# kugarem.net
KiCad netlist of a schematic drawn in EAGLE
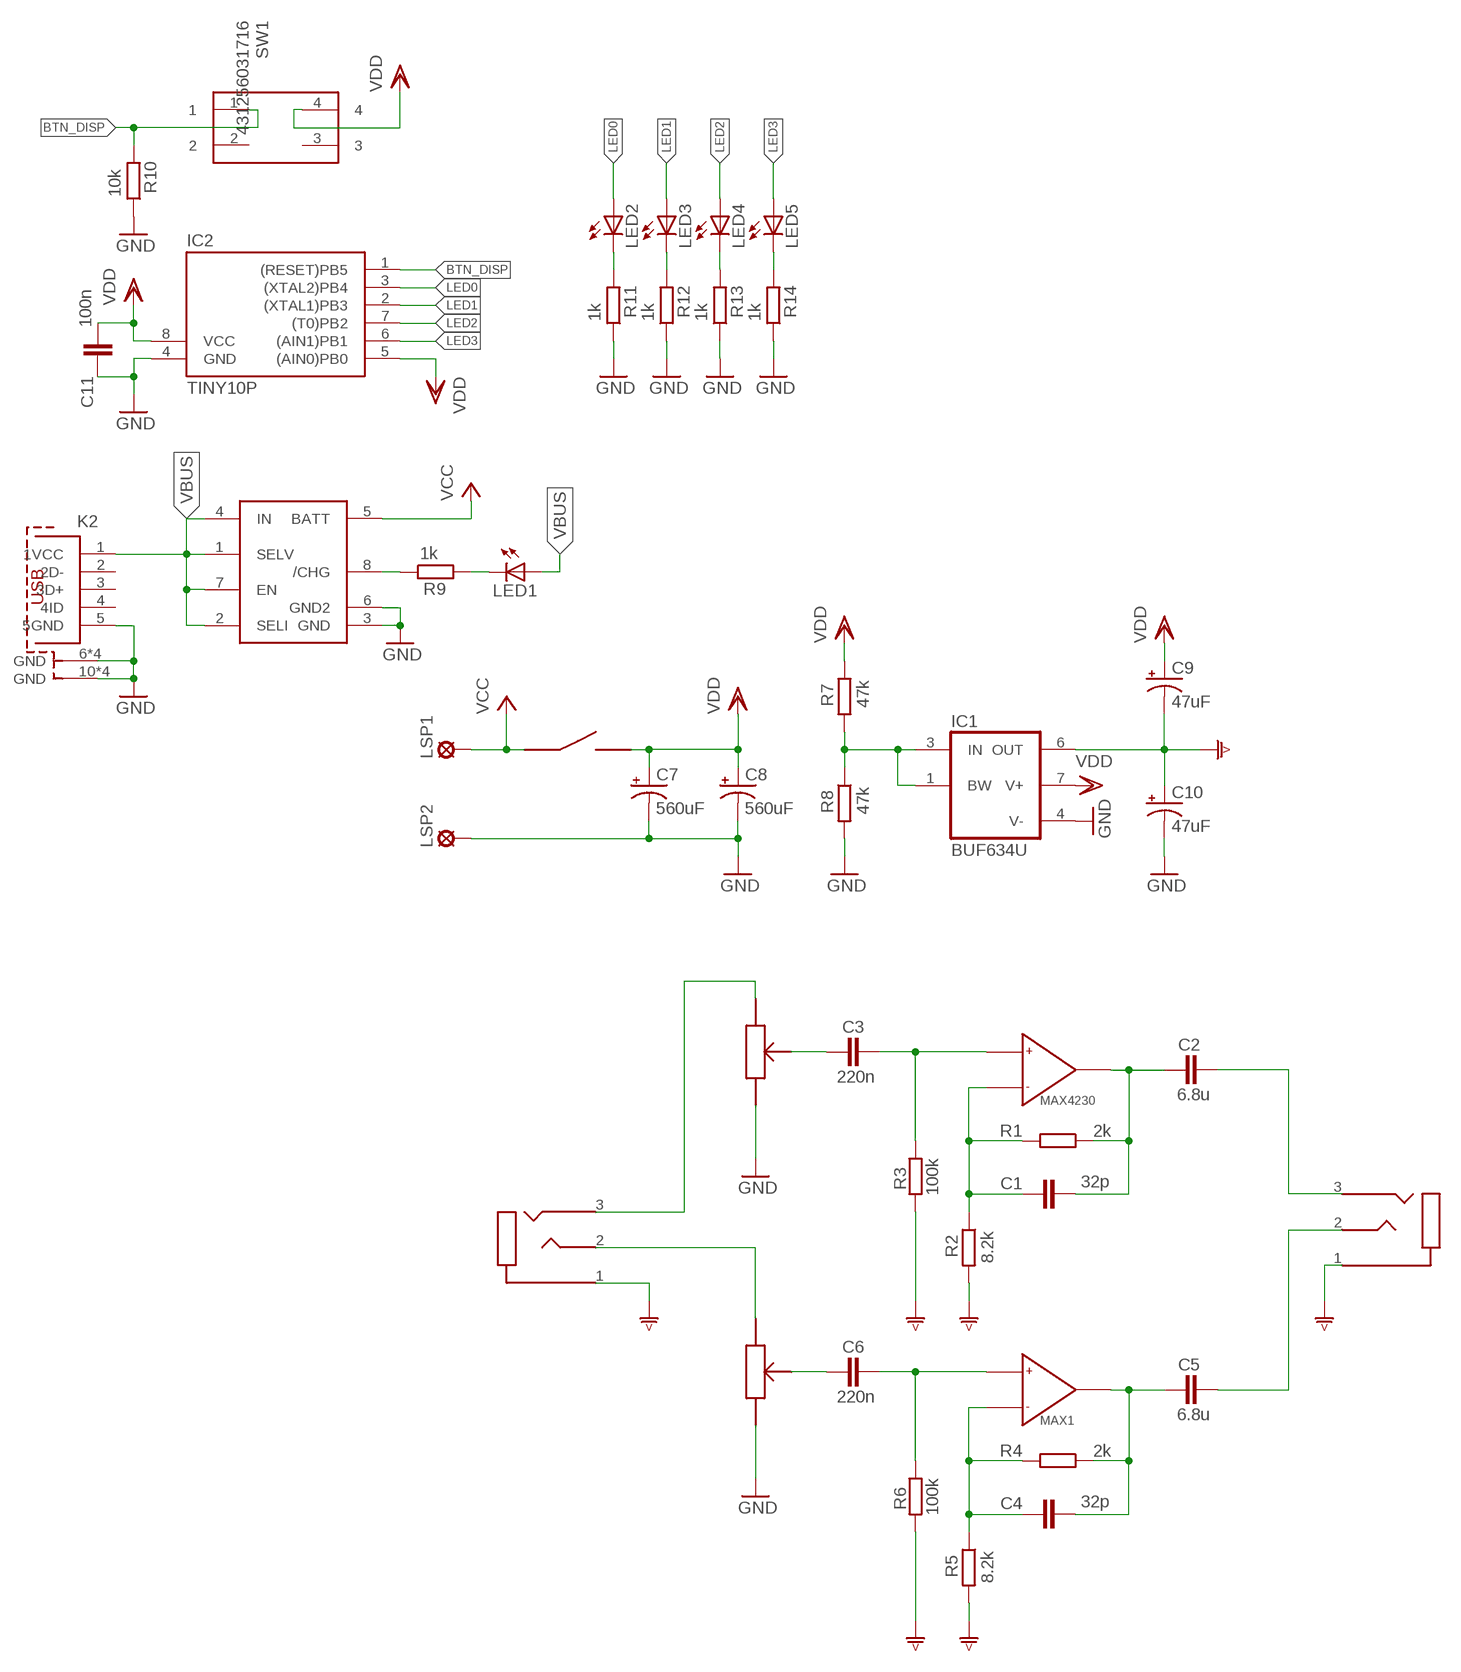
[diagram p0: schematic, sheet 1]

(export (version "E")
  (design (tool "Eeschema 10.0.6"))
  (components
    (comp (ref "C1")
      (value "32p")
      (footprint "eagle-import:C1206")
      (libsource (lib "eagle-import") (part "C-EUC1206"))
    )
    (comp (ref "C2")
      (value "6.8u")
      (footprint "eagle-import:C1206")
      (libsource (lib "eagle-import") (part "C-EUC1206"))
    )
    (comp (ref "C3")
      (value "220n")
      (footprint "eagle-import:C1206")
      (libsource (lib "eagle-import") (part "C-EUC1206"))
    )
    (comp (ref "C4")
      (value "32p")
      (footprint "eagle-import:C1206")
      (libsource (lib "eagle-import") (part "C-EUC1206"))
    )
    (comp (ref "C5")
      (value "6.8u")
      (footprint "eagle-import:C1206")
      (libsource (lib "eagle-import") (part "C-EUC1206"))
    )
    (comp (ref "C6")
      (value "220n")
      (footprint "eagle-import:C1206")
      (libsource (lib "eagle-import") (part "C-EUC1206"))
    )
    (comp (ref "C7")
      (value "560uF")
      (footprint "eagle-import:PANASONIC_G")
      (libsource (lib "eagle-import") (part "560UF-PANASONIC_G-25V-20%"))
    )
    (comp (ref "C8")
      (value "560uF")
      (footprint "eagle-import:PANASONIC_G")
      (libsource (lib "eagle-import") (part "560UF-PANASONIC_G-25V-20%"))
    )
    (comp (ref "C9")
      (value "47uF")
      (footprint "eagle-import:PANASONIC_D")
      (libsource (lib "eagle-import") (part "47UF-POLAR-PANASONIC_D-35V-20%"))
    )
    (comp (ref "C10")
      (value "47uF")
      (footprint "eagle-import:PANASONIC_D")
      (libsource (lib "eagle-import") (part "47UF-POLAR-PANASONIC_D-35V-20%"))
    )
    (comp (ref "C11")
      (value "100n")
      (footprint "eagle-import:C1206")
      (libsource (lib "eagle-import") (part "C-EUC1206"))
    )
    (comp (ref "IC1")
      (value "BUF634U")
      (footprint "eagle-import:SO08")
      (fields (field (name "MF") "TEXAS INSTRUMENTS"))
      (libsource (lib "eagle-import") (part "BUF634U"))
    )
    (comp (ref "IC2")
      (value "TINY10P")
      (footprint "eagle-import:DIL08")
      (libsource (lib "eagle-import") (part "TINY10P"))
    )
    (comp (ref "K2")
      (value "629105150921")
      (footprint "eagle-import:629105150921")
      (libsource (lib "eagle-import") (part "629105150921"))
    )
    (comp (ref "LED1")
      (value "LEDCHIPLED_1206")
      (footprint "eagle-import:CHIPLED_1206")
      (libsource (lib "eagle-import") (part "LEDCHIPLED_1206"))
    )
    (comp (ref "LED2")
      (value "LEDCHIPLED_1206")
      (footprint "eagle-import:CHIPLED_1206")
      (libsource (lib "eagle-import") (part "LEDCHIPLED_1206"))
    )
    (comp (ref "LED3")
      (value "LEDCHIPLED_1206")
      (footprint "eagle-import:CHIPLED_1206")
      (libsource (lib "eagle-import") (part "LEDCHIPLED_1206"))
    )
    (comp (ref "LED4")
      (value "LEDCHIPLED_1206")
      (footprint "eagle-import:CHIPLED_1206")
      (libsource (lib "eagle-import") (part "LEDCHIPLED_1206"))
    )
    (comp (ref "LED5")
      (value "LEDCHIPLED_1206")
      (footprint "eagle-import:CHIPLED_1206")
      (libsource (lib "eagle-import") (part "LEDCHIPLED_1206"))
    )
    (comp (ref "LSP1")
      (value "LSP10")
      (footprint "eagle-import:LSP10")
      (libsource (lib "eagle-import") (part "LSP10"))
    )
    (comp (ref "LSP2")
      (value "LSP10")
      (footprint "eagle-import:LSP10")
      (libsource (lib "eagle-import") (part "LSP10"))
    )
    (comp (ref "MAX1")
      (value "MAX4230")
      (footprint "eagle-import:SOT23-5L")
      (libsource (lib "eagle-import") (part "MAX4230"))
    )
    (comp (ref "MAX4230")
      (value "MAX4230")
      (footprint "eagle-import:SOT23-5L")
      (libsource (lib "eagle-import") (part "MAX4230"))
    )
    (comp (ref "R1")
      (value "2k")
      (footprint "eagle-import:R1206")
      (libsource (lib "eagle-import") (part "R-EU_R1206"))
    )
    (comp (ref "R2")
      (value "8.2k")
      (footprint "eagle-import:R1206")
      (libsource (lib "eagle-import") (part "R-EU_R1206"))
    )
    (comp (ref "R3")
      (value "100k")
      (footprint "eagle-import:R1206")
      (libsource (lib "eagle-import") (part "R-EU_R1206"))
    )
    (comp (ref "R4")
      (value "2k")
      (footprint "eagle-import:R1206")
      (libsource (lib "eagle-import") (part "R-EU_R1206"))
    )
    (comp (ref "R5")
      (value "8.2k")
      (footprint "eagle-import:R1206")
      (libsource (lib "eagle-import") (part "R-EU_R1206"))
    )
    (comp (ref "R6")
      (value "100k")
      (footprint "eagle-import:R1206")
      (libsource (lib "eagle-import") (part "R-EU_R1206"))
    )
    (comp (ref "R7")
      (value "47k")
      (footprint "eagle-import:R1206")
      (libsource (lib "eagle-import") (part "R-EU_R1206"))
    )
    (comp (ref "R8")
      (value "47k")
      (footprint "eagle-import:R1206")
      (libsource (lib "eagle-import") (part "R-EU_R1206"))
    )
    (comp (ref "R9")
      (value "1k")
      (footprint "eagle-import:R1206")
      (libsource (lib "eagle-import") (part "R-EU_R1206"))
    )
    (comp (ref "R10")
      (value "10k")
      (footprint "eagle-import:R1206")
      (libsource (lib "eagle-import") (part "R-EU_R1206"))
    )
    (comp (ref "R11")
      (value "1k")
      (footprint "eagle-import:R1206")
      (libsource (lib "eagle-import") (part "R-EU_R1206"))
    )
    (comp (ref "R12")
      (value "1k")
      (footprint "eagle-import:R1206")
      (libsource (lib "eagle-import") (part "R-EU_R1206"))
    )
    (comp (ref "R13")
      (value "1k")
      (footprint "eagle-import:R1206")
      (libsource (lib "eagle-import") (part "R-EU_R1206"))
    )
    (comp (ref "R14")
      (value "1k")
      (footprint "eagle-import:R1206")
      (libsource (lib "eagle-import") (part "R-EU_R1206"))
    )
    (comp (ref "SW1")
      (value "431256031716")
      (footprint "eagle-import:431256031716")
      (libsource (lib "eagle-import") (part "431256031716"))
    )
    (comp (ref "U$1")
      (value "100k")
      (footprint "eagle-import:PTR902")
      (libsource (lib "eagle-import") (part "PTR90"))
    )
    (comp (ref "U$2")
      (value "SJ1-3515-SMT-TR")
      (footprint "eagle-import:STX-35332-3N-TR")
      (libsource (lib "eagle-import") (part "SJ1-3515-SMT-TR"))
    )
    (comp (ref "U$3")
      (value "SJ1-3515-SMT-TR")
      (footprint "eagle-import:STX-35332-3N-TR")
      (libsource (lib "eagle-import") (part "SJ1-3515-SMT-TR"))
    )
    (comp (ref "U$4")
      (value "MAX1811SO8")
      (footprint "eagle-import:SO08")
      (libsource (lib "eagle-import") (part "MAX1811SO8"))
    )
  )
  (nets
    (net (code "1") (name "BTN_DISP") (class "Default")
      (node (ref "IC2") (pin "1") (pinfunction "(RESET)PB5_1") (pintype "bidirectional"))
      (node (ref "R10") (pin "2") (pinfunction "2_2") (pintype "passive"))
      (node (ref "SW1") (pin "1") (pinfunction "1_1") (pintype "bidirectional"))
    )
    (net (code "2") (name "GND") (class "Default")
      (node (ref "C10") (pin "-") (pinfunction "-_-") (pintype "passive"))
      (node (ref "C11") (pin "1") (pinfunction "1_1") (pintype "passive"))
      (node (ref "C7") (pin "-") (pinfunction "-_-") (pintype "passive"))
      (node (ref "C8") (pin "-") (pinfunction "-_-") (pintype "passive"))
      (node (ref "IC1") (pin "4") (pinfunction "V-_4") (pintype "power_in"))
      (node (ref "IC2") (pin "4") (pinfunction "GND_4") (pintype "power_in"))
      (node (ref "K2") (pin "10") (pinfunction "GND_10") (pintype "bidirectional"))
      (node (ref "K2") (pin "11") (pinfunction "GND_11") (pintype "bidirectional"))
      (node (ref "K2") (pin "12") (pinfunction "GND_12") (pintype "bidirectional"))
      (node (ref "K2") (pin "13") (pinfunction "GND_13") (pintype "bidirectional"))
      (node (ref "K2") (pin "5") (pinfunction "5GND_5") (pintype "passive"))
      (node (ref "K2") (pin "6") (pinfunction "GND_6") (pintype "bidirectional"))
      (node (ref "K2") (pin "7") (pinfunction "GND_7") (pintype "bidirectional"))
      (node (ref "K2") (pin "8") (pinfunction "GND_8") (pintype "bidirectional"))
      (node (ref "K2") (pin "9") (pinfunction "GND_9") (pintype "bidirectional"))
      (node (ref "LSP2") (pin "MP") (pinfunction "MP_MP") (pintype "passive"))
      (node (ref "R10") (pin "1") (pinfunction "1_1") (pintype "passive"))
      (node (ref "R11") (pin "1") (pinfunction "1_1") (pintype "passive"))
      (node (ref "R12") (pin "1") (pinfunction "1_1") (pintype "passive"))
      (node (ref "R13") (pin "1") (pinfunction "1_1") (pintype "passive"))
      (node (ref "R14") (pin "1") (pinfunction "1_1") (pintype "passive"))
      (node (ref "R8") (pin "2") (pinfunction "2_2") (pintype "passive"))
      (node (ref "U$1") (pin "R13") (pinfunction "13_R13") (pintype "bidirectional"))
      (node (ref "U$1") (pin "R23") (pinfunction "13_R23") (pintype "bidirectional"))
      (node (ref "U$4") (pin "3") (pinfunction "GND_3") (pintype "bidirectional"))
      (node (ref "U$4") (pin "6") (pinfunction "GND2_6") (pintype "bidirectional"))
    )
    (net (code "3") (name "LED0") (class "Default")
      (node (ref "IC2") (pin "3") (pinfunction "(XTAL2)PB4_3") (pintype "bidirectional"))
      (node (ref "LED2") (pin "A") (pinfunction "A_A") (pintype "passive"))
    )
    (net (code "4") (name "LED1") (class "Default")
      (node (ref "IC2") (pin "2") (pinfunction "(XTAL1)PB3_2") (pintype "bidirectional"))
      (node (ref "LED3") (pin "A") (pinfunction "A_A") (pintype "passive"))
    )
    (net (code "5") (name "LED2") (class "Default")
      (node (ref "IC2") (pin "7") (pinfunction "(T0)PB2_7") (pintype "bidirectional"))
      (node (ref "LED4") (pin "A") (pinfunction "A_A") (pintype "passive"))
    )
    (net (code "6") (name "LED3") (class "Default")
      (node (ref "IC2") (pin "6") (pinfunction "(AIN1)PB1_6") (pintype "bidirectional"))
      (node (ref "LED5") (pin "A") (pinfunction "A_A") (pintype "passive"))
    )
    (net (code "7") (name "Net-(IC1-BW)") (class "Default")
      (node (ref "IC1") (pin "1") (pinfunction "BW_1") (pintype "passive"))
      (node (ref "IC1") (pin "3") (pinfunction "IN_3") (pintype "input"))
      (node (ref "R7") (pin "2") (pinfunction "2_2") (pintype "passive"))
      (node (ref "R8") (pin "1") (pinfunction "1_1") (pintype "passive"))
    )
    (net (code "8") (name "Net-(LED1-PadC)") (class "Default")
      (node (ref "LED1") (pin "C") (pinfunction "C_C") (pintype "passive"))
      (node (ref "R9") (pin "2") (pinfunction "2_2") (pintype "passive"))
    )
    (net (code "9") (name "Net-(LED2-PadC)") (class "Default")
      (node (ref "LED2") (pin "C") (pinfunction "C_C") (pintype "passive"))
      (node (ref "R11") (pin "2") (pinfunction "2_2") (pintype "passive"))
    )
    (net (code "10") (name "Net-(LED3-PadC)") (class "Default")
      (node (ref "LED3") (pin "C") (pinfunction "C_C") (pintype "passive"))
      (node (ref "R12") (pin "2") (pinfunction "2_2") (pintype "passive"))
    )
    (net (code "11") (name "Net-(LED4-PadC)") (class "Default")
      (node (ref "LED4") (pin "C") (pinfunction "C_C") (pintype "passive"))
      (node (ref "R13") (pin "2") (pinfunction "2_2") (pintype "passive"))
    )
    (net (code "12") (name "Net-(LED5-PadC)") (class "Default")
      (node (ref "LED5") (pin "C") (pinfunction "C_C") (pintype "passive"))
      (node (ref "R14") (pin "2") (pinfunction "2_2") (pintype "passive"))
    )
    (net (code "13") (name "Net-(MAX1A-IN+)") (class "Default")
      (node (ref "C6") (pin "2") (pinfunction "2_2") (pintype "passive"))
      (node (ref "MAX1") (pin "1") (pinfunction "IN+_1") (pintype "bidirectional"))
      (node (ref "R6") (pin "1") (pinfunction "1_1") (pintype "passive"))
    )
    (net (code "14") (name "Net-(MAX1A-IN-)") (class "Default")
      (node (ref "C4") (pin "1") (pinfunction "1_1") (pintype "passive"))
      (node (ref "MAX1") (pin "3") (pinfunction "IN-_3") (pintype "bidirectional"))
      (node (ref "R4") (pin "2") (pinfunction "2_2") (pintype "passive"))
      (node (ref "R5") (pin "1") (pinfunction "1_1") (pintype "passive"))
    )
    (net (code "15") (name "Net-(MAX1A-OUT)") (class "Default")
      (node (ref "C4") (pin "2") (pinfunction "2_2") (pintype "passive"))
      (node (ref "C5") (pin "1") (pinfunction "1_1") (pintype "passive"))
      (node (ref "MAX1") (pin "4") (pinfunction "OUT_4") (pintype "bidirectional"))
      (node (ref "R4") (pin "1") (pinfunction "1_1") (pintype "passive"))
    )
    (net (code "16") (name "Net-(MAX4230A-IN+)") (class "Default")
      (node (ref "C3") (pin "2") (pinfunction "2_2") (pintype "passive"))
      (node (ref "MAX4230") (pin "1") (pinfunction "IN+_1") (pintype "bidirectional"))
      (node (ref "R3") (pin "1") (pinfunction "1_1") (pintype "passive"))
    )
    (net (code "17") (name "Net-(MAX4230A-IN-)") (class "Default")
      (node (ref "C1") (pin "1") (pinfunction "1_1") (pintype "passive"))
      (node (ref "MAX4230") (pin "3") (pinfunction "IN-_3") (pintype "bidirectional"))
      (node (ref "R1") (pin "2") (pinfunction "2_2") (pintype "passive"))
      (node (ref "R2") (pin "1") (pinfunction "1_1") (pintype "passive"))
    )
    (net (code "18") (name "Net-(MAX4230A-OUT)") (class "Default")
      (node (ref "C1") (pin "2") (pinfunction "2_2") (pintype "passive"))
      (node (ref "C2") (pin "1") (pinfunction "1_1") (pintype "passive"))
      (node (ref "MAX4230") (pin "4") (pinfunction "OUT_4") (pintype "bidirectional"))
      (node (ref "R1") (pin "1") (pinfunction "1_1") (pintype "passive"))
    )
    (net (code "19") (name "Net-(U$1A-11)") (class "Default")
      (node (ref "U$1") (pin "R11") (pinfunction "11_R11") (pintype "bidirectional"))
      (node (ref "U$2") (pin "2") (pinfunction "TIP_2") (pintype "bidirectional"))
    )
    (net (code "20") (name "Net-(U$1A-12)") (class "Default")
      (node (ref "C6") (pin "1") (pinfunction "1_1") (pintype "passive"))
      (node (ref "U$1") (pin "R12") (pinfunction "12_R12") (pintype "bidirectional"))
    )
    (net (code "21") (name "Net-(U$1B-11)") (class "Default")
      (node (ref "U$1") (pin "R21") (pinfunction "11_R21") (pintype "bidirectional"))
      (node (ref "U$2") (pin "3") (pinfunction "RING_3") (pintype "bidirectional"))
    )
    (net (code "22") (name "Net-(U$1B-12)") (class "Default")
      (node (ref "C3") (pin "1") (pinfunction "1_1") (pintype "passive"))
      (node (ref "U$1") (pin "R22") (pinfunction "12_R22") (pintype "bidirectional"))
    )
    (net (code "23") (name "Net-(U$3-RING)") (class "Default")
      (node (ref "C2") (pin "2") (pinfunction "2_2") (pintype "passive"))
      (node (ref "U$3") (pin "3") (pinfunction "RING_3") (pintype "bidirectional"))
    )
    (net (code "24") (name "Net-(U$3-TIP)") (class "Default")
      (node (ref "C5") (pin "2") (pinfunction "2_2") (pintype "passive"))
      (node (ref "U$3") (pin "2") (pinfunction "TIP_2") (pintype "bidirectional"))
    )
    (net (code "25") (name "Net-(U$4-{slash}CHG)") (class "Default")
      (node (ref "R9") (pin "1") (pinfunction "1_1") (pintype "passive"))
      (node (ref "U$4") (pin "8") (pinfunction "/CHG_8") (pintype "bidirectional"))
    )
    (net (code "26") (name "VBUS") (class "Default")
      (node (ref "K2") (pin "1") (pinfunction "1VCC_1") (pintype "passive"))
      (node (ref "LED1") (pin "A") (pinfunction "A_A") (pintype "passive"))
      (node (ref "U$4") (pin "1") (pinfunction "SELV_1") (pintype "bidirectional"))
      (node (ref "U$4") (pin "2") (pinfunction "SELI_2") (pintype "bidirectional"))
      (node (ref "U$4") (pin "4") (pinfunction "IN_4") (pintype "bidirectional"))
      (node (ref "U$4") (pin "7") (pinfunction "EN_7") (pintype "bidirectional"))
    )
    (net (code "27") (name "VCC") (class "Default")
      (node (ref "LSP1") (pin "MP") (pinfunction "MP_MP") (pintype "passive"))
      (node (ref "U$1") (pin "SW1") (pinfunction "11_SW1") (pintype "bidirectional"))
      (node (ref "U$4") (pin "5") (pinfunction "BATT_5") (pintype "bidirectional"))
    )
    (net (code "28") (name "VDD") (class "Default")
      (node (ref "C11") (pin "2") (pinfunction "2_2") (pintype "passive"))
      (node (ref "C7") (pin "+") (pinfunction "+_+") (pintype "passive"))
      (node (ref "C8") (pin "+") (pinfunction "+_+") (pintype "passive"))
      (node (ref "C9") (pin "+") (pinfunction "+_+") (pintype "passive"))
      (node (ref "IC1") (pin "7") (pinfunction "V+_7") (pintype "power_in"))
      (node (ref "IC2") (pin "5") (pinfunction "(AIN0)PB0_5") (pintype "bidirectional"))
      (node (ref "IC2") (pin "8") (pinfunction "VCC_8") (pintype "power_in"))
      (node (ref "R7") (pin "1") (pinfunction "1_1") (pintype "passive"))
      (node (ref "SW1") (pin "4") (pinfunction "4_4") (pintype "bidirectional"))
      (node (ref "U$1") (pin "SW2") (pinfunction "12_SW2") (pintype "bidirectional"))
    )
    (net (code "29") (name "VGND") (class "Default")
      (node (ref "C10") (pin "+") (pinfunction "+_+") (pintype "passive"))
      (node (ref "C9") (pin "-") (pinfunction "-_-") (pintype "passive"))
      (node (ref "IC1") (pin "6") (pinfunction "OUT_6") (pintype "output"))
      (node (ref "R2") (pin "2") (pinfunction "2_2") (pintype "passive"))
      (node (ref "R3") (pin "2") (pinfunction "2_2") (pintype "passive"))
      (node (ref "R5") (pin "2") (pinfunction "2_2") (pintype "passive"))
      (node (ref "R6") (pin "2") (pinfunction "2_2") (pintype "passive"))
      (node (ref "U$2") (pin "1") (pinfunction "SLEEVE_1") (pintype "bidirectional"))
      (node (ref "U$3") (pin "1") (pinfunction "SLEEVE_1") (pintype "bidirectional"))
    )
    (net (code "30") (name "unconnected-(K2-2D--Pad2)") (class "Default")
      (node (ref "K2") (pin "2") (pinfunction "2D-_2") (pintype "passive"))
    )
    (net (code "31") (name "unconnected-(K2-3D+-Pad3)") (class "Default")
      (node (ref "K2") (pin "3") (pinfunction "3D+_3") (pintype "passive"))
    )
    (net (code "32") (name "unconnected-(K2-4ID-Pad4)") (class "Default")
      (node (ref "K2") (pin "4") (pinfunction "4ID_4") (pintype "passive"))
    )
    (net (code "33") (name "unconnected-(SW1-Pad2)") (class "Default")
      (node (ref "SW1") (pin "2") (pinfunction "2_2") (pintype "bidirectional"))
    )
    (net (code "34") (name "unconnected-(SW1-Pad3)") (class "Default")
      (node (ref "SW1") (pin "3") (pinfunction "3_3") (pintype "bidirectional"))
    )
  )
)
